# comparator_circuit.net
KiCad netlist of a schematic drawn in EAGLE
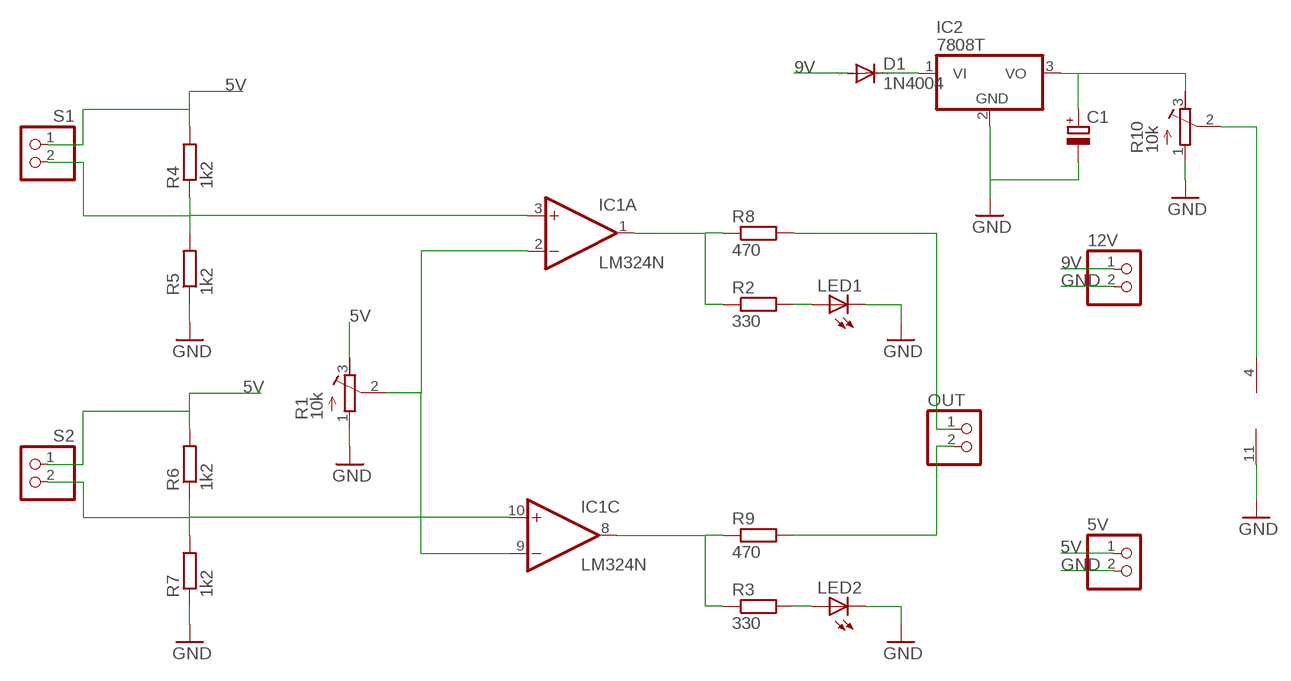
[diagram p0: schematic, sheet 1]

(export (version "E")
  (design (tool "Eeschema 10.0.6"))
  (components
    (comp (ref "5V")
      (value "PINHD-1X2")
      (footprint "eagle-import:1X02")
      (libsource (lib "eagle-import") (part "PINHD-1X2"))
    )
    (comp (ref "12V")
      (value "PINHD-1X2")
      (footprint "eagle-import:1X02")
      (libsource (lib "eagle-import") (part "PINHD-1X2"))
    )
    (comp (ref "C1")
      (value "CPOL-EUE2.5-6")
      (footprint "eagle-import:E2,5-6")
      (libsource (lib "eagle-import") (part "CPOL-EUE2.5-6"))
    )
    (comp (ref "D1")
      (value "1N4004")
      (footprint "eagle-import:DO41-10")
      (libsource (lib "eagle-import") (part "1N4004"))
    )
    (comp (ref "IC1")
      (value "LM324N")
      (footprint "eagle-import:DIL14")
      (libsource (lib "eagle-import") (part "LM324N"))
    )
    (comp (ref "IC2")
      (value "7808T")
      (footprint "eagle-import:TO220H")
      (libsource (lib "eagle-import") (part "78T08"))
    )
    (comp (ref "LED1")
      (value "LED3MM")
      (footprint "eagle-import:LED3MM")
      (libsource (lib "eagle-import") (part "LED3MM"))
    )
    (comp (ref "LED2")
      (value "LED3MM")
      (footprint "eagle-import:LED3MM")
      (libsource (lib "eagle-import") (part "LED3MM"))
    )
    (comp (ref "OUT")
      (value "PINHD-1X2")
      (footprint "eagle-import:1X02")
      (libsource (lib "eagle-import") (part "PINHD-1X2"))
    )
    (comp (ref "R1")
      (value "10k")
      (footprint "eagle-import:RTRIM3339P")
      (libsource (lib "eagle-import") (part "R-TRIMM3339P"))
    )
    (comp (ref "R2")
      (value "330")
      (footprint "eagle-import:0204_7")
      (libsource (lib "eagle-import") (part "R-EU_0204/7"))
    )
    (comp (ref "R3")
      (value "330")
      (footprint "eagle-import:0204_7")
      (libsource (lib "eagle-import") (part "R-EU_0204/7"))
    )
    (comp (ref "R4")
      (value "1k2")
      (footprint "eagle-import:0204_7")
      (libsource (lib "eagle-import") (part "R-EU_0204/7"))
    )
    (comp (ref "R5")
      (value "1k2")
      (footprint "eagle-import:0204_7")
      (libsource (lib "eagle-import") (part "R-EU_0204/7"))
    )
    (comp (ref "R6")
      (value "1k2")
      (footprint "eagle-import:0204_7")
      (libsource (lib "eagle-import") (part "R-EU_0204/7"))
    )
    (comp (ref "R7")
      (value "1k2")
      (footprint "eagle-import:0204_7")
      (libsource (lib "eagle-import") (part "R-EU_0204/7"))
    )
    (comp (ref "R8")
      (value "470")
      (footprint "eagle-import:0204_7")
      (libsource (lib "eagle-import") (part "R-EU_0204/7"))
    )
    (comp (ref "R9")
      (value "470")
      (footprint "eagle-import:0204_7")
      (libsource (lib "eagle-import") (part "R-EU_0204/7"))
    )
    (comp (ref "R10")
      (value "10k")
      (footprint "eagle-import:RTRIM3339P")
      (libsource (lib "eagle-import") (part "R-TRIMM3339P"))
    )
    (comp (ref "S1")
      (value "PINHD-1X2")
      (footprint "eagle-import:1X02")
      (libsource (lib "eagle-import") (part "PINHD-1X2"))
    )
    (comp (ref "S2")
      (value "PINHD-1X2")
      (footprint "eagle-import:1X02")
      (libsource (lib "eagle-import") (part "PINHD-1X2"))
    )
  )
  (nets
    (net (code "1") (name "/5V") (class "Default")
      (node (ref "5V") (pin "1") (pinfunction "1_1") (pintype "passive"))
      (node (ref "R1") (pin "3") (pinfunction "E_3") (pintype "passive"))
      (node (ref "R4") (pin "2") (pinfunction "2_2") (pintype "passive"))
      (node (ref "R6") (pin "2") (pinfunction "2_2") (pintype "passive"))
      (node (ref "S1") (pin "1") (pinfunction "1_1") (pintype "passive"))
      (node (ref "S2") (pin "1") (pinfunction "1_1") (pintype "passive"))
    )
    (net (code "2") (name "/9V") (class "Default")
      (node (ref "12V") (pin "1") (pinfunction "1_1") (pintype "passive"))
      (node (ref "D1") (pin "A") (pinfunction "A_A") (pintype "passive"))
    )
    (net (code "3") (name "GND") (class "Default")
      (node (ref "12V") (pin "2") (pinfunction "2_2") (pintype "passive"))
      (node (ref "5V") (pin "2") (pinfunction "2_2") (pintype "passive"))
      (node (ref "C1") (pin "-") (pinfunction "-_-") (pintype "passive"))
      (node (ref "IC1") (pin "11") (pinfunction "V-_11") (pintype "power_in"))
      (node (ref "IC2") (pin "2") (pinfunction "GND_2") (pintype "passive"))
      (node (ref "LED1") (pin "K") (pinfunction "C_K") (pintype "passive"))
      (node (ref "LED2") (pin "K") (pinfunction "C_K") (pintype "passive"))
      (node (ref "R1") (pin "1") (pinfunction "A_1") (pintype "passive"))
      (node (ref "R10") (pin "1") (pinfunction "A_1") (pintype "passive"))
      (node (ref "R5") (pin "1") (pinfunction "1_1") (pintype "passive"))
      (node (ref "R7") (pin "1") (pinfunction "1_1") (pintype "passive"))
    )
    (net (code "4") (name "Net-(IC1A-+IN)") (class "Default")
      (node (ref "IC1") (pin "3") (pinfunction "+IN_3") (pintype "input"))
      (node (ref "R4") (pin "1") (pinfunction "1_1") (pintype "passive"))
      (node (ref "R5") (pin "2") (pinfunction "2_2") (pintype "passive"))
      (node (ref "S1") (pin "2") (pinfunction "2_2") (pintype "passive"))
    )
    (net (code "5") (name "Net-(IC1A--IN)") (class "Default")
      (node (ref "IC1") (pin "2") (pinfunction "-IN_2") (pintype "input"))
      (node (ref "IC1") (pin "9") (pinfunction "-IN_9") (pintype "input"))
      (node (ref "R1") (pin "2") (pinfunction "S_2") (pintype "passive"))
    )
    (net (code "6") (name "Net-(IC1A-OUT)") (class "Default")
      (node (ref "IC1") (pin "1") (pinfunction "OUT_1") (pintype "output"))
      (node (ref "R2") (pin "1") (pinfunction "1_1") (pintype "passive"))
      (node (ref "R8") (pin "1") (pinfunction "1_1") (pintype "passive"))
    )
    (net (code "7") (name "Net-(IC1C-+IN)") (class "Default")
      (node (ref "IC1") (pin "10") (pinfunction "+IN_10") (pintype "input"))
      (node (ref "R6") (pin "1") (pinfunction "1_1") (pintype "passive"))
      (node (ref "R7") (pin "2") (pinfunction "2_2") (pintype "passive"))
      (node (ref "S2") (pin "2") (pinfunction "2_2") (pintype "passive"))
    )
    (net (code "8") (name "Net-(IC1C-OUT)") (class "Default")
      (node (ref "IC1") (pin "8") (pinfunction "OUT_8") (pintype "output"))
      (node (ref "R3") (pin "1") (pinfunction "1_1") (pintype "passive"))
      (node (ref "R9") (pin "1") (pinfunction "1_1") (pintype "passive"))
    )
    (net (code "9") (name "Net-(IC1E-V+)") (class "Default")
      (node (ref "IC1") (pin "4") (pinfunction "V+_4") (pintype "power_in"))
      (node (ref "R10") (pin "2") (pinfunction "S_2") (pintype "passive"))
    )
    (net (code "10") (name "Net-(IC2-VI)") (class "Default")
      (node (ref "D1") (pin "C") (pinfunction "C_C") (pintype "passive"))
      (node (ref "IC2") (pin "1") (pinfunction "VI_1") (pintype "input"))
    )
    (net (code "11") (name "Net-(IC2-VO)") (class "Default")
      (node (ref "C1") (pin "+") (pinfunction "+_+") (pintype "passive"))
      (node (ref "IC2") (pin "3") (pinfunction "VO_3") (pintype "passive"))
      (node (ref "R10") (pin "3") (pinfunction "E_3") (pintype "passive"))
    )
    (net (code "12") (name "Net-(LED1-PadA)") (class "Default")
      (node (ref "LED1") (pin "A") (pinfunction "A_A") (pintype "passive"))
      (node (ref "R2") (pin "2") (pinfunction "2_2") (pintype "passive"))
    )
    (net (code "13") (name "Net-(LED2-PadA)") (class "Default")
      (node (ref "LED2") (pin "A") (pinfunction "A_A") (pintype "passive"))
      (node (ref "R3") (pin "2") (pinfunction "2_2") (pintype "passive"))
    )
    (net (code "14") (name "Net-(OUT-Pad1)") (class "Default")
      (node (ref "OUT") (pin "1") (pinfunction "1_1") (pintype "passive"))
      (node (ref "R8") (pin "2") (pinfunction "2_2") (pintype "passive"))
    )
    (net (code "15") (name "Net-(OUT-Pad2)") (class "Default")
      (node (ref "OUT") (pin "2") (pinfunction "2_2") (pintype "passive"))
      (node (ref "R9") (pin "2") (pinfunction "2_2") (pintype "passive"))
    )
  )
)
